# SAML21_Breakout_v2.net
KiCad netlist of a schematic drawn in EAGLE
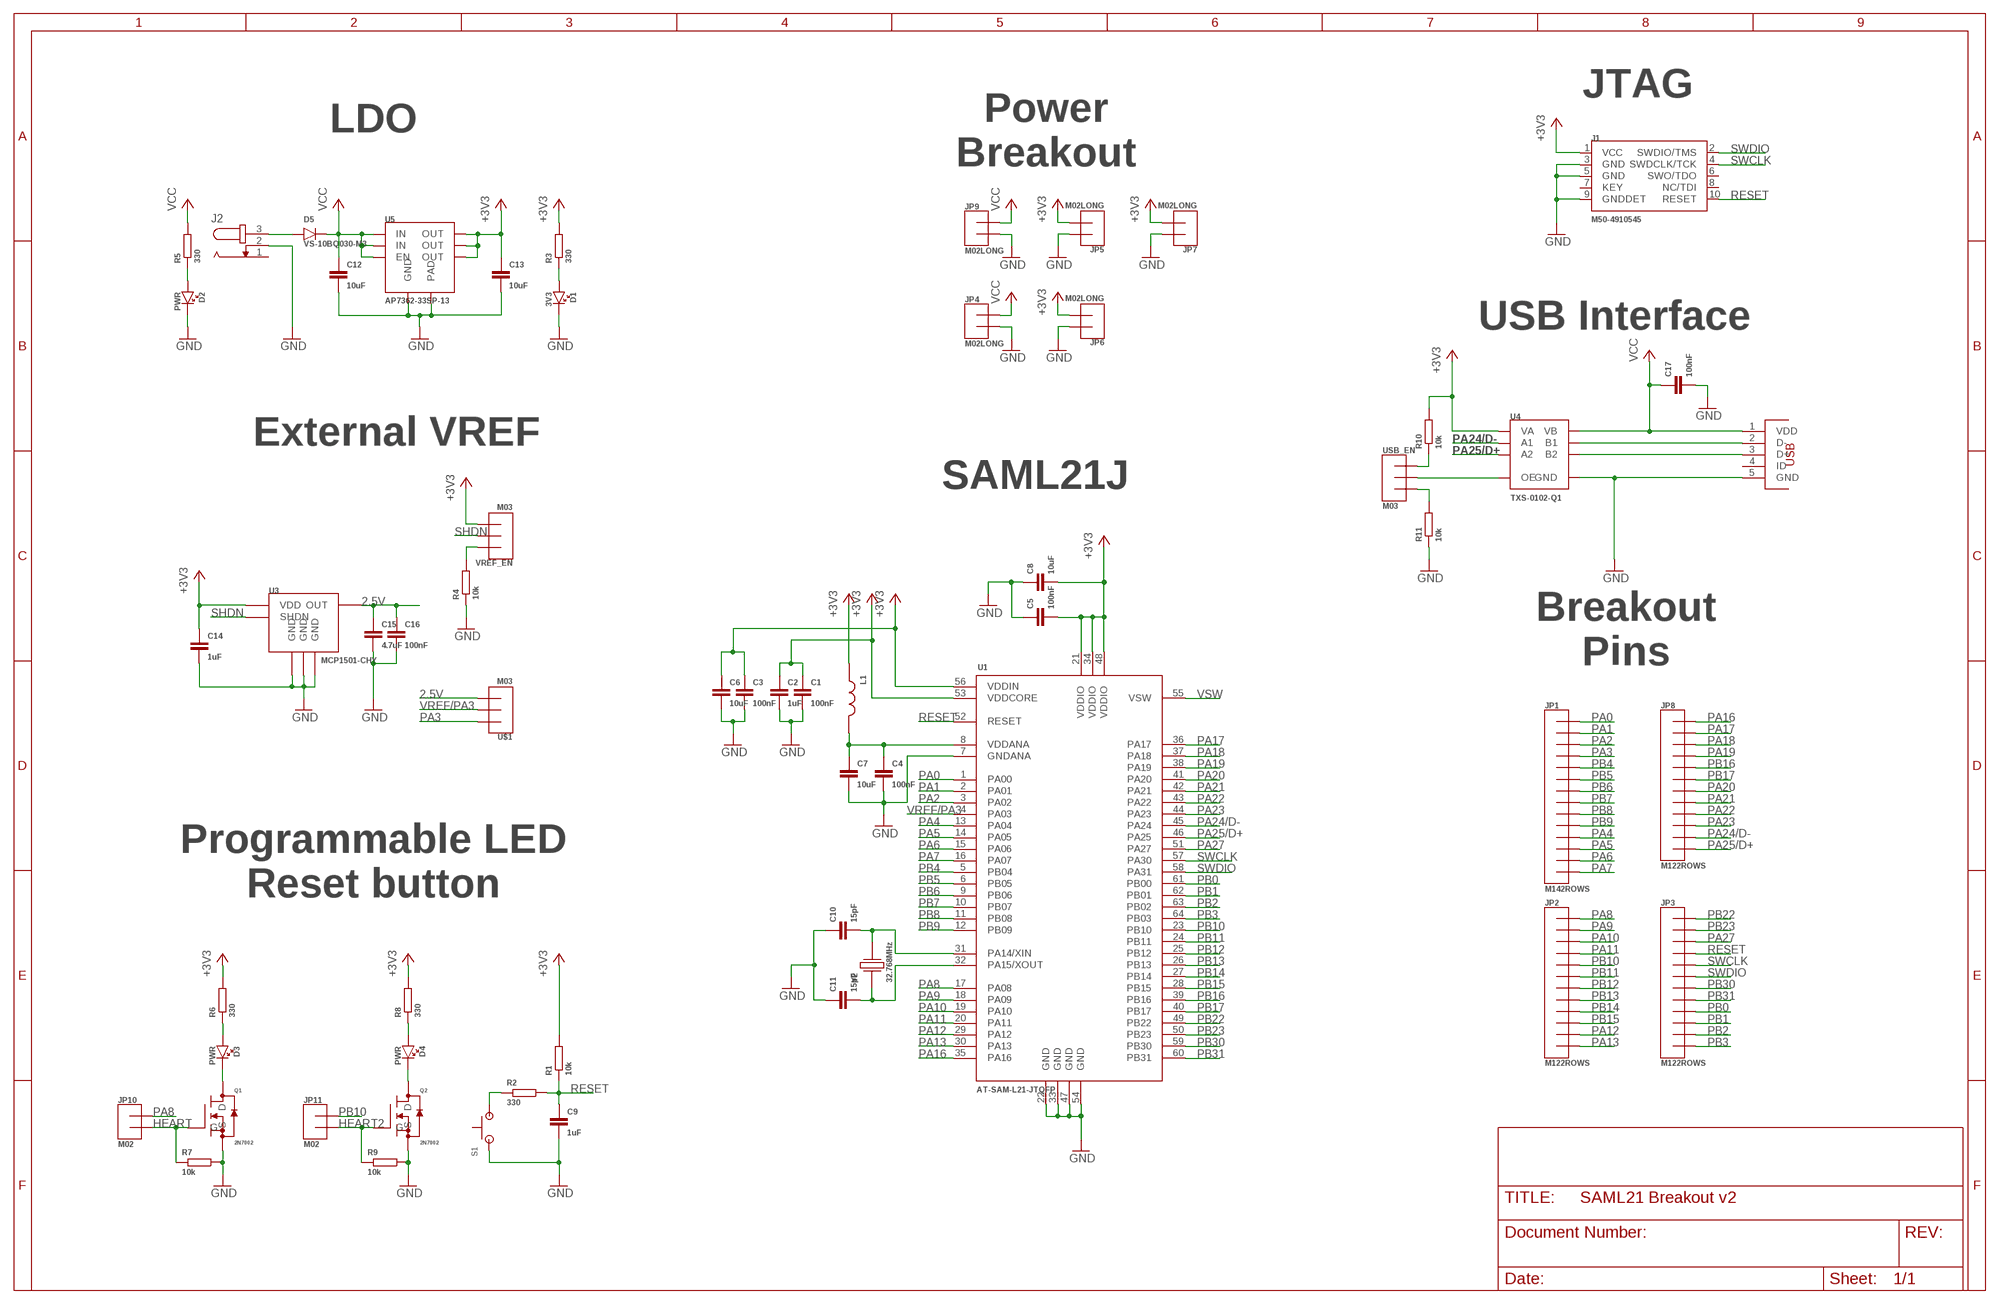
[diagram p0: schematic, sheet 1]

(export (version "E")
  (design (tool "Eeschema 10.0.6"))
  (components
    (comp (ref "C1")
      (value "100nF")
      (footprint "eagle-import:CAP-0603")
      (libsource (lib "eagle-import") (part "CAP0603"))
    )
    (comp (ref "C2")
      (value "1uF")
      (footprint "eagle-import:CAP-0603")
      (libsource (lib "eagle-import") (part "CAP0603"))
    )
    (comp (ref "C3")
      (value "100nF")
      (footprint "eagle-import:CAP-0603")
      (libsource (lib "eagle-import") (part "CAP0603"))
    )
    (comp (ref "C4")
      (value "100nF")
      (footprint "eagle-import:CAP-0603")
      (libsource (lib "eagle-import") (part "CAP0603"))
    )
    (comp (ref "C5")
      (value "100nF")
      (footprint "eagle-import:CAP-0603")
      (libsource (lib "eagle-import") (part "CAP0603"))
    )
    (comp (ref "C6")
      (value "10uF")
      (footprint "eagle-import:CAP-0603")
      (libsource (lib "eagle-import") (part "CAP0603"))
    )
    (comp (ref "C7")
      (value "10uF")
      (footprint "eagle-import:CAP-0603")
      (libsource (lib "eagle-import") (part "CAP0603"))
    )
    (comp (ref "C8")
      (value "10uF")
      (footprint "eagle-import:CAP-0603")
      (libsource (lib "eagle-import") (part "CAP0603"))
    )
    (comp (ref "C9")
      (value "1uF")
      (footprint "eagle-import:CAP-0603")
      (libsource (lib "eagle-import") (part "CAP0603"))
    )
    (comp (ref "C10")
      (value "15pF")
      (footprint "eagle-import:CAP-0603")
      (libsource (lib "eagle-import") (part "CAP0603"))
    )
    (comp (ref "C11")
      (value "15pF")
      (footprint "eagle-import:CAP-0603")
      (libsource (lib "eagle-import") (part "CAP0603"))
    )
    (comp (ref "C12")
      (value "10uF")
      (footprint "eagle-import:CAP-0603")
      (libsource (lib "eagle-import") (part "CAP0603"))
    )
    (comp (ref "C13")
      (value "10uF")
      (footprint "eagle-import:CAP-0603")
      (libsource (lib "eagle-import") (part "CAP0603"))
    )
    (comp (ref "C14")
      (value "1uF")
      (footprint "eagle-import:CAP-0603")
      (libsource (lib "eagle-import") (part "CAP0603"))
    )
    (comp (ref "C15")
      (value "4.7uF")
      (footprint "eagle-import:CAP-0805")
      (libsource (lib "eagle-import") (part "CAP0805"))
    )
    (comp (ref "C16")
      (value "100nF")
      (footprint "eagle-import:CAP-0603")
      (libsource (lib "eagle-import") (part "CAP0603"))
    )
    (comp (ref "C17")
      (value "100nF")
      (footprint "eagle-import:CAP-0603")
      (libsource (lib "eagle-import") (part "CAP0603"))
    )
    (comp (ref "D1")
      (value "3V3")
      (footprint "eagle-import:LED-1206")
      (libsource (lib "eagle-import") (part "LED1206"))
    )
    (comp (ref "D2")
      (value "PWR")
      (footprint "eagle-import:LED-1206")
      (libsource (lib "eagle-import") (part "LED1206"))
    )
    (comp (ref "D3")
      (value "PWR")
      (footprint "eagle-import:LED-1206")
      (libsource (lib "eagle-import") (part "LED1206"))
    )
    (comp (ref "D4")
      (value "PWR")
      (footprint "eagle-import:LED-1206")
      (libsource (lib "eagle-import") (part "LED1206"))
    )
    (comp (ref "D5")
      (value "VS-10BQ030-M3")
      (footprint "eagle-import:DO-214AA")
      (libsource (lib "eagle-import") (part "VS-10BQ030-M3"))
    )
    (comp (ref "J1")
      (value "M50-4910545")
      (footprint "eagle-import:M50-4910545")
      (libsource (lib "eagle-import") (part "M50-4910545"))
    )
    (comp (ref "J2")
      (value "JACK-PLUG0")
      (footprint "eagle-import:SPC4077")
      (libsource (lib "eagle-import") (part "JACK-PLUG0"))
    )
    (comp (ref "JP1")
      (value "M142ROWS")
      (footprint "eagle-import:2X07")
      (libsource (lib "eagle-import") (part "M142ROWS"))
    )
    (comp (ref "JP2")
      (value "M122ROWS")
      (footprint "eagle-import:2X06")
      (libsource (lib "eagle-import") (part "M122ROWS"))
    )
    (comp (ref "JP3")
      (value "M122ROWS")
      (footprint "eagle-import:2X06")
      (libsource (lib "eagle-import") (part "M122ROWS"))
    )
    (comp (ref "JP4")
      (value "M02LONG")
      (footprint "eagle-import:1X02-LONG")
      (libsource (lib "eagle-import") (part "M02LONG"))
    )
    (comp (ref "JP5")
      (value "M02LONG")
      (footprint "eagle-import:1X02-LONG")
      (libsource (lib "eagle-import") (part "M02LONG"))
    )
    (comp (ref "JP6")
      (value "M02LONG")
      (footprint "eagle-import:1X02-LONG")
      (libsource (lib "eagle-import") (part "M02LONG"))
    )
    (comp (ref "JP7")
      (value "M02LONG")
      (footprint "eagle-import:1X02-LONG")
      (libsource (lib "eagle-import") (part "M02LONG"))
    )
    (comp (ref "JP8")
      (value "M122ROWS")
      (footprint "eagle-import:2X06")
      (libsource (lib "eagle-import") (part "M122ROWS"))
    )
    (comp (ref "JP9")
      (value "M02LONG")
      (footprint "eagle-import:1X02-LONG")
      (libsource (lib "eagle-import") (part "M02LONG"))
    )
    (comp (ref "JP10")
      (value "M02")
      (footprint "eagle-import:1X02")
      (libsource (lib "eagle-import") (part "M02"))
    )
    (comp (ref "JP11")
      (value "M02")
      (footprint "eagle-import:1X02")
      (libsource (lib "eagle-import") (part "M02"))
    )
    (comp (ref "L1")
      (value "INDUCTOR0603")
      (footprint "eagle-import:IND-0603")
      (libsource (lib "eagle-import") (part "INDUCTOR0603"))
    )
    (comp (ref "Q1")
      (value "2N7002")
      (footprint "eagle-import:SOT-23-3")
      (libsource (lib "eagle-import") (part "2N7002"))
    )
    (comp (ref "Q2")
      (value "2N7002")
      (footprint "eagle-import:SOT-23-3")
      (libsource (lib "eagle-import") (part "2N7002"))
    )
    (comp (ref "R1")
      (value "10k")
      (footprint "eagle-import:RES-0805")
      (libsource (lib "eagle-import") (part "RESISTOR0805"))
    )
    (comp (ref "R2")
      (value "330")
      (footprint "eagle-import:RES-0805")
      (libsource (lib "eagle-import") (part "RESISTOR0805"))
    )
    (comp (ref "R3")
      (value "330")
      (footprint "eagle-import:RES-0805")
      (libsource (lib "eagle-import") (part "RESISTOR0805"))
    )
    (comp (ref "R4")
      (value "10k")
      (footprint "eagle-import:RES-0805")
      (libsource (lib "eagle-import") (part "RESISTOR0805"))
    )
    (comp (ref "R5")
      (value "330")
      (footprint "eagle-import:RES-0805")
      (libsource (lib "eagle-import") (part "RESISTOR0805"))
    )
    (comp (ref "R6")
      (value "330")
      (footprint "eagle-import:RES-0805")
      (libsource (lib "eagle-import") (part "RESISTOR0805"))
    )
    (comp (ref "R7")
      (value "10k")
      (footprint "eagle-import:RES-0805")
      (libsource (lib "eagle-import") (part "RESISTOR0805"))
    )
    (comp (ref "R8")
      (value "330")
      (footprint "eagle-import:RES-0805")
      (libsource (lib "eagle-import") (part "RESISTOR0805"))
    )
    (comp (ref "R9")
      (value "10k")
      (footprint "eagle-import:RES-0805")
      (libsource (lib "eagle-import") (part "RESISTOR0805"))
    )
    (comp (ref "R10")
      (value "10k")
      (footprint "eagle-import:RES-0805")
      (libsource (lib "eagle-import") (part "RESISTOR0805"))
    )
    (comp (ref "R11")
      (value "10k")
      (footprint "eagle-import:RES-0805")
      (libsource (lib "eagle-import") (part "RESISTOR0805"))
    )
    (comp (ref "S1")
      (value "SKHMQME010")
      (footprint "eagle-import:SKHMQME010")
      (libsource (lib "eagle-import") (part "SKHMQME010"))
    )
    (comp (ref "U$1")
      (value "M03")
      (footprint "eagle-import:1X03")
      (libsource (lib "eagle-import") (part "M03"))
    )
    (comp (ref "U$6")
      (value "MOLEX_USBMICRO")
      (footprint "eagle-import:MOLEX_47346-001")
      (libsource (lib "eagle-import") (part "MOLEX_USBMICRO"))
    )
    (comp (ref "U1")
      (value "AT-SAM-L21-JTQFP")
      (footprint "eagle-import:TQFP-64")
      (libsource (lib "eagle-import") (part "AT-SAM-L21-JTQFP"))
    )
    (comp (ref "U3")
      (value "MCP1501-CHY")
      (footprint "eagle-import:SOT-23-6")
      (libsource (lib "eagle-import") (part "MCP1501-CHY"))
    )
    (comp (ref "U4")
      (value "TXS-0102-Q1")
      (footprint "eagle-import:VSSOP-8")
      (libsource (lib "eagle-import") (part "TXS-0102-Q1"))
    )
    (comp (ref "U5")
      (value "AP7362-33SP-13")
      (footprint "eagle-import:SO-8EP")
      (libsource (lib "eagle-import") (part "AP7362-33SP-13"))
    )
    (comp (ref "USB_EN")
      (value "M03")
      (footprint "eagle-import:1X03")
      (libsource (lib "eagle-import") (part "M03"))
    )
    (comp (ref "VREF_EN")
      (value "M03")
      (footprint "eagle-import:1X03")
      (libsource (lib "eagle-import") (part "M03"))
    )
    (comp (ref "Y2")
      (value "32.768MHz")
      (footprint "eagle-import:CFPX-217")
      (libsource (lib "eagle-import") (part "LFXTAL054236-R"))
    )
  )
  (nets
    (net (code "1") (name "+3V3") (class "Default")
      (node (ref "C1") (pin "1") (pinfunction "1_1") (pintype "passive"))
      (node (ref "C13") (pin "1") (pinfunction "1_1") (pintype "passive"))
      (node (ref "C14") (pin "1") (pinfunction "1_1") (pintype "passive"))
      (node (ref "C2") (pin "1") (pinfunction "1_1") (pintype "passive"))
      (node (ref "C3") (pin "1") (pinfunction "1_1") (pintype "passive"))
      (node (ref "C5") (pin "2") (pinfunction "2_2") (pintype "passive"))
      (node (ref "C6") (pin "1") (pinfunction "1_1") (pintype "passive"))
      (node (ref "C8") (pin "2") (pinfunction "2_2") (pintype "passive"))
      (node (ref "J1") (pin "1") (pinfunction "VCC_1") (pintype "bidirectional"))
      (node (ref "JP5") (pin "2") (pinfunction "2_2") (pintype "bidirectional"))
      (node (ref "JP6") (pin "2") (pinfunction "2_2") (pintype "bidirectional"))
      (node (ref "JP7") (pin "2") (pinfunction "2_2") (pintype "bidirectional"))
      (node (ref "L1") (pin "1") (pinfunction "1_1") (pintype "passive"))
      (node (ref "R1") (pin "2") (pinfunction "2_2") (pintype "passive"))
      (node (ref "R10") (pin "2") (pinfunction "2_2") (pintype "passive"))
      (node (ref "R3") (pin "2") (pinfunction "2_2") (pintype "passive"))
      (node (ref "R6") (pin "2") (pinfunction "2_2") (pintype "passive"))
      (node (ref "R8") (pin "2") (pinfunction "2_2") (pintype "passive"))
      (node (ref "U1") (pin "21") (pinfunction "VDDIO_21") (pintype "power_in"))
      (node (ref "U1") (pin "34") (pinfunction "VDDIO_34") (pintype "power_in"))
      (node (ref "U1") (pin "48") (pinfunction "VDDIO_48") (pintype "power_in"))
      (node (ref "U1") (pin "53") (pinfunction "VDDCORE_53") (pintype "output"))
      (node (ref "U1") (pin "56") (pinfunction "VDDIN_56") (pintype "power_in"))
      (node (ref "U3") (pin "6") (pinfunction "VDD_6") (pintype "bidirectional"))
      (node (ref "U4") (pin "3") (pinfunction "VA_3") (pintype "bidirectional"))
      (node (ref "U5") (pin "5") (pinfunction "OUT_5") (pintype "bidirectional"))
      (node (ref "U5") (pin "6") (pinfunction "OUT_6") (pintype "bidirectional"))
      (node (ref "U5") (pin "7") (pinfunction "OUT_7") (pintype "bidirectional"))
      (node (ref "VREF_EN") (pin "3") (pinfunction "3_3") (pintype "bidirectional"))
    )
    (net (code "2") (name "/2.5V") (class "Default")
      (node (ref "C15") (pin "1") (pinfunction "1_1") (pintype "passive"))
      (node (ref "C16") (pin "1") (pinfunction "1_1") (pintype "passive"))
      (node (ref "U$1") (pin "3") (pinfunction "3_3") (pintype "bidirectional"))
      (node (ref "U3") (pin "1") (pinfunction "OUT_1") (pintype "bidirectional"))
    )
    (net (code "3") (name "/HEART") (class "Default")
      (node (ref "JP10") (pin "2") (pinfunction "2_2") (pintype "bidirectional"))
      (node (ref "Q1") (pin "G") (pinfunction "G_G") (pintype "bidirectional"))
      (node (ref "R7") (pin "1") (pinfunction "1_1") (pintype "passive"))
    )
    (net (code "4") (name "/HEART2") (class "Default")
      (node (ref "JP11") (pin "2") (pinfunction "2_2") (pintype "bidirectional"))
      (node (ref "Q2") (pin "G") (pinfunction "G_G") (pintype "bidirectional"))
      (node (ref "R9") (pin "1") (pinfunction "1_1") (pintype "passive"))
    )
    (net (code "5") (name "/PA0") (class "Default")
      (node (ref "JP1") (pin "1") (pinfunction "1_1") (pintype "bidirectional"))
      (node (ref "U1") (pin "1") (pinfunction "PA00_1") (pintype "bidirectional"))
    )
    (net (code "6") (name "/PA1") (class "Default")
      (node (ref "JP1") (pin "2") (pinfunction "2_2") (pintype "bidirectional"))
      (node (ref "U1") (pin "2") (pinfunction "PA01_2") (pintype "bidirectional"))
    )
    (net (code "7") (name "/PA2") (class "Default")
      (node (ref "JP1") (pin "3") (pinfunction "3_3") (pintype "bidirectional"))
      (node (ref "U1") (pin "3") (pinfunction "PA02_3") (pintype "bidirectional"))
    )
    (net (code "8") (name "/PA3") (class "Default")
      (node (ref "JP1") (pin "4") (pinfunction "4_4") (pintype "bidirectional"))
      (node (ref "U$1") (pin "1") (pinfunction "1_1") (pintype "bidirectional"))
    )
    (net (code "9") (name "/PA4") (class "Default")
      (node (ref "JP1") (pin "11") (pinfunction "11_11") (pintype "bidirectional"))
      (node (ref "U1") (pin "13") (pinfunction "PA04_13") (pintype "bidirectional"))
    )
    (net (code "10") (name "/PA5") (class "Default")
      (node (ref "JP1") (pin "12") (pinfunction "12_12") (pintype "bidirectional"))
      (node (ref "U1") (pin "14") (pinfunction "PA05_14") (pintype "bidirectional"))
    )
    (net (code "11") (name "/PA6") (class "Default")
      (node (ref "JP1") (pin "13") (pinfunction "13_13") (pintype "bidirectional"))
      (node (ref "U1") (pin "15") (pinfunction "PA06_15") (pintype "bidirectional"))
    )
    (net (code "12") (name "/PA7") (class "Default")
      (node (ref "JP1") (pin "14") (pinfunction "14_14") (pintype "bidirectional"))
      (node (ref "U1") (pin "16") (pinfunction "PA07_16") (pintype "bidirectional"))
    )
    (net (code "13") (name "/PA8") (class "Default")
      (node (ref "JP10") (pin "1") (pinfunction "1_1") (pintype "bidirectional"))
      (node (ref "JP2") (pin "1") (pinfunction "1_1") (pintype "bidirectional"))
      (node (ref "U1") (pin "17") (pinfunction "PA08_17") (pintype "bidirectional"))
    )
    (net (code "14") (name "/PA9") (class "Default")
      (node (ref "JP2") (pin "2") (pinfunction "2_2") (pintype "bidirectional"))
      (node (ref "U1") (pin "18") (pinfunction "PA09_18") (pintype "bidirectional"))
    )
    (net (code "15") (name "/PA10") (class "Default")
      (node (ref "JP2") (pin "3") (pinfunction "3_3") (pintype "bidirectional"))
      (node (ref "U1") (pin "19") (pinfunction "PA10_19") (pintype "bidirectional"))
    )
    (net (code "16") (name "/PA11") (class "Default")
      (node (ref "JP2") (pin "4") (pinfunction "4_4") (pintype "bidirectional"))
      (node (ref "U1") (pin "20") (pinfunction "PA11_20") (pintype "bidirectional"))
    )
    (net (code "17") (name "/PA12") (class "Default")
      (node (ref "JP2") (pin "11") (pinfunction "11_11") (pintype "bidirectional"))
      (node (ref "U1") (pin "29") (pinfunction "PA12_29") (pintype "bidirectional"))
    )
    (net (code "18") (name "/PA13") (class "Default")
      (node (ref "JP2") (pin "12") (pinfunction "12_12") (pintype "bidirectional"))
      (node (ref "U1") (pin "30") (pinfunction "PA13_30") (pintype "bidirectional"))
    )
    (net (code "19") (name "/PA16") (class "Default")
      (node (ref "JP8") (pin "1") (pinfunction "1_1") (pintype "bidirectional"))
      (node (ref "U1") (pin "35") (pinfunction "PA16_35") (pintype "bidirectional"))
    )
    (net (code "20") (name "/PA17") (class "Default")
      (node (ref "JP8") (pin "2") (pinfunction "2_2") (pintype "bidirectional"))
      (node (ref "U1") (pin "36") (pinfunction "PA17_36") (pintype "bidirectional"))
    )
    (net (code "21") (name "/PA18") (class "Default")
      (node (ref "JP8") (pin "3") (pinfunction "3_3") (pintype "bidirectional"))
      (node (ref "U1") (pin "37") (pinfunction "PA18_37") (pintype "bidirectional"))
    )
    (net (code "22") (name "/PA19") (class "Default")
      (node (ref "JP8") (pin "4") (pinfunction "4_4") (pintype "bidirectional"))
      (node (ref "U1") (pin "38") (pinfunction "PA19_38") (pintype "bidirectional"))
    )
    (net (code "23") (name "/PA20") (class "Default")
      (node (ref "JP8") (pin "7") (pinfunction "7_7") (pintype "bidirectional"))
      (node (ref "U1") (pin "41") (pinfunction "PA20_41") (pintype "bidirectional"))
    )
    (net (code "24") (name "/PA21") (class "Default")
      (node (ref "JP8") (pin "8") (pinfunction "8_8") (pintype "bidirectional"))
      (node (ref "U1") (pin "42") (pinfunction "PA21_42") (pintype "bidirectional"))
    )
    (net (code "25") (name "/PA22") (class "Default")
      (node (ref "JP8") (pin "9") (pinfunction "9_9") (pintype "bidirectional"))
      (node (ref "U1") (pin "43") (pinfunction "PA22_43") (pintype "bidirectional"))
    )
    (net (code "26") (name "/PA23") (class "Default")
      (node (ref "JP8") (pin "10") (pinfunction "10_10") (pintype "bidirectional"))
      (node (ref "U1") (pin "44") (pinfunction "PA23_44") (pintype "bidirectional"))
    )
    (net (code "27") (name "/PA24{slash}D-") (class "Default")
      (node (ref "JP8") (pin "11") (pinfunction "11_11") (pintype "bidirectional"))
      (node (ref "U1") (pin "45") (pinfunction "PA24_45") (pintype "bidirectional"))
      (node (ref "U4") (pin "5") (pinfunction "A1_5") (pintype "bidirectional"))
    )
    (net (code "28") (name "/PA25{slash}D+") (class "Default")
      (node (ref "JP8") (pin "12") (pinfunction "12_12") (pintype "bidirectional"))
      (node (ref "U1") (pin "46") (pinfunction "PA25_46") (pintype "bidirectional"))
      (node (ref "U4") (pin "4") (pinfunction "A2_4") (pintype "bidirectional"))
    )
    (net (code "29") (name "/PA27") (class "Default")
      (node (ref "JP3") (pin "3") (pinfunction "3_3") (pintype "bidirectional"))
      (node (ref "U1") (pin "51") (pinfunction "PA27_51") (pintype "bidirectional"))
    )
    (net (code "30") (name "/PB0") (class "Default")
      (node (ref "JP3") (pin "9") (pinfunction "9_9") (pintype "bidirectional"))
      (node (ref "U1") (pin "61") (pinfunction "PB00_61") (pintype "bidirectional"))
    )
    (net (code "31") (name "/PB1") (class "Default")
      (node (ref "JP3") (pin "10") (pinfunction "10_10") (pintype "bidirectional"))
      (node (ref "U1") (pin "62") (pinfunction "PB01_62") (pintype "bidirectional"))
    )
    (net (code "32") (name "/PB2") (class "Default")
      (node (ref "JP3") (pin "11") (pinfunction "11_11") (pintype "bidirectional"))
      (node (ref "U1") (pin "63") (pinfunction "PB02_63") (pintype "bidirectional"))
    )
    (net (code "33") (name "/PB3") (class "Default")
      (node (ref "JP3") (pin "12") (pinfunction "12_12") (pintype "bidirectional"))
      (node (ref "U1") (pin "64") (pinfunction "PB03_64") (pintype "bidirectional"))
    )
    (net (code "34") (name "/PB4") (class "Default")
      (node (ref "JP1") (pin "5") (pinfunction "5_5") (pintype "bidirectional"))
      (node (ref "U1") (pin "5") (pinfunction "PB04_5") (pintype "bidirectional"))
    )
    (net (code "35") (name "/PB5") (class "Default")
      (node (ref "JP1") (pin "6") (pinfunction "6_6") (pintype "bidirectional"))
      (node (ref "U1") (pin "6") (pinfunction "PB05_6") (pintype "bidirectional"))
    )
    (net (code "36") (name "/PB6") (class "Default")
      (node (ref "JP1") (pin "7") (pinfunction "7_7") (pintype "bidirectional"))
      (node (ref "U1") (pin "9") (pinfunction "PB06_9") (pintype "bidirectional"))
    )
    (net (code "37") (name "/PB7") (class "Default")
      (node (ref "JP1") (pin "8") (pinfunction "8_8") (pintype "bidirectional"))
      (node (ref "U1") (pin "10") (pinfunction "PB07_10") (pintype "bidirectional"))
    )
    (net (code "38") (name "/PB8") (class "Default")
      (node (ref "JP1") (pin "9") (pinfunction "9_9") (pintype "bidirectional"))
      (node (ref "U1") (pin "11") (pinfunction "PB08_11") (pintype "bidirectional"))
    )
    (net (code "39") (name "/PB9") (class "Default")
      (node (ref "JP1") (pin "10") (pinfunction "10_10") (pintype "bidirectional"))
      (node (ref "U1") (pin "12") (pinfunction "PB09_12") (pintype "bidirectional"))
    )
    (net (code "40") (name "/PB10") (class "Default")
      (node (ref "JP11") (pin "1") (pinfunction "1_1") (pintype "bidirectional"))
      (node (ref "JP2") (pin "5") (pinfunction "5_5") (pintype "bidirectional"))
      (node (ref "U1") (pin "23") (pinfunction "PB10_23") (pintype "bidirectional"))
    )
    (net (code "41") (name "/PB11") (class "Default")
      (node (ref "JP2") (pin "6") (pinfunction "6_6") (pintype "bidirectional"))
      (node (ref "U1") (pin "24") (pinfunction "PB11_24") (pintype "bidirectional"))
    )
    (net (code "42") (name "/PB12") (class "Default")
      (node (ref "JP2") (pin "7") (pinfunction "7_7") (pintype "bidirectional"))
      (node (ref "U1") (pin "25") (pinfunction "PB12_25") (pintype "bidirectional"))
    )
    (net (code "43") (name "/PB13") (class "Default")
      (node (ref "JP2") (pin "8") (pinfunction "8_8") (pintype "bidirectional"))
      (node (ref "U1") (pin "26") (pinfunction "PB13_26") (pintype "bidirectional"))
    )
    (net (code "44") (name "/PB14") (class "Default")
      (node (ref "JP2") (pin "9") (pinfunction "9_9") (pintype "bidirectional"))
      (node (ref "U1") (pin "27") (pinfunction "PB14_27") (pintype "bidirectional"))
    )
    (net (code "45") (name "/PB15") (class "Default")
      (node (ref "JP2") (pin "10") (pinfunction "10_10") (pintype "bidirectional"))
      (node (ref "U1") (pin "28") (pinfunction "PB15_28") (pintype "bidirectional"))
    )
    (net (code "46") (name "/PB16") (class "Default")
      (node (ref "JP8") (pin "5") (pinfunction "5_5") (pintype "bidirectional"))
      (node (ref "U1") (pin "39") (pinfunction "PB16_39") (pintype "bidirectional"))
    )
    (net (code "47") (name "/PB17") (class "Default")
      (node (ref "JP8") (pin "6") (pinfunction "6_6") (pintype "bidirectional"))
      (node (ref "U1") (pin "40") (pinfunction "PB17_40") (pintype "bidirectional"))
    )
    (net (code "48") (name "/PB22") (class "Default")
      (node (ref "JP3") (pin "1") (pinfunction "1_1") (pintype "bidirectional"))
      (node (ref "U1") (pin "49") (pinfunction "PB22_49") (pintype "bidirectional"))
    )
    (net (code "49") (name "/PB23") (class "Default")
      (node (ref "JP3") (pin "2") (pinfunction "2_2") (pintype "bidirectional"))
      (node (ref "U1") (pin "50") (pinfunction "PB23_50") (pintype "bidirectional"))
    )
    (net (code "50") (name "/PB30") (class "Default")
      (node (ref "JP3") (pin "7") (pinfunction "7_7") (pintype "bidirectional"))
      (node (ref "U1") (pin "59") (pinfunction "PB30_59") (pintype "bidirectional"))
    )
    (net (code "51") (name "/PB31") (class "Default")
      (node (ref "JP3") (pin "8") (pinfunction "8_8") (pintype "bidirectional"))
      (node (ref "U1") (pin "60") (pinfunction "PB31_60") (pintype "bidirectional"))
    )
    (net (code "52") (name "/RESET") (class "Default")
      (node (ref "C9") (pin "1") (pinfunction "1_1") (pintype "passive"))
      (node (ref "J1") (pin "10") (pinfunction "RESET_10") (pintype "bidirectional"))
      (node (ref "JP3") (pin "4") (pinfunction "4_4") (pintype "bidirectional"))
      (node (ref "R1") (pin "1") (pinfunction "1_1") (pintype "passive"))
      (node (ref "R2") (pin "2") (pinfunction "2_2") (pintype "passive"))
      (node (ref "U1") (pin "52") (pinfunction "RESET_52") (pintype "bidirectional"))
    )
    (net (code "53") (name "/SHDN") (class "Default")
      (node (ref "U3") (pin "4") (pinfunction "SHDN_4") (pintype "bidirectional"))
      (node (ref "VREF_EN") (pin "2") (pinfunction "2_2") (pintype "bidirectional"))
    )
    (net (code "54") (name "/SWCLK") (class "Default")
      (node (ref "J1") (pin "4") (pinfunction "SWDCLK/TCK_4") (pintype "bidirectional"))
      (node (ref "JP3") (pin "5") (pinfunction "5_5") (pintype "bidirectional"))
      (node (ref "U1") (pin "57") (pinfunction "PA30_57") (pintype "bidirectional"))
    )
    (net (code "55") (name "/SWDIO") (class "Default")
      (node (ref "J1") (pin "2") (pinfunction "SWDIO/TMS_2") (pintype "bidirectional"))
      (node (ref "JP3") (pin "6") (pinfunction "6_6") (pintype "bidirectional"))
      (node (ref "U1") (pin "58") (pinfunction "PA31_58") (pintype "bidirectional"))
    )
    (net (code "56") (name "/VREF{slash}PA3") (class "Default")
      (node (ref "U$1") (pin "2") (pinfunction "2_2") (pintype "bidirectional"))
      (node (ref "U1") (pin "4") (pinfunction "PA03_4") (pintype "bidirectional"))
    )
    (net (code "57") (name "/VSW") (class "Default")
      (node (ref "U1") (pin "55") (pinfunction "VSW_55") (pintype "bidirectional"))
    )
    (net (code "58") (name "GND") (class "Default")
      (node (ref "C1") (pin "2") (pinfunction "2_2") (pintype "passive"))
      (node (ref "C10") (pin "1") (pinfunction "1_1") (pintype "passive"))
      (node (ref "C11") (pin "1") (pinfunction "1_1") (pintype "passive"))
      (node (ref "C12") (pin "2") (pinfunction "2_2") (pintype "passive"))
      (node (ref "C13") (pin "2") (pinfunction "2_2") (pintype "passive"))
      (node (ref "C14") (pin "2") (pinfunction "2_2") (pintype "passive"))
      (node (ref "C15") (pin "2") (pinfunction "2_2") (pintype "passive"))
      (node (ref "C16") (pin "2") (pinfunction "2_2") (pintype "passive"))
      (node (ref "C17") (pin "2") (pinfunction "2_2") (pintype "passive"))
      (node (ref "C2") (pin "2") (pinfunction "2_2") (pintype "passive"))
      (node (ref "C3") (pin "2") (pinfunction "2_2") (pintype "passive"))
      (node (ref "C4") (pin "2") (pinfunction "2_2") (pintype "passive"))
      (node (ref "C5") (pin "1") (pinfunction "1_1") (pintype "passive"))
      (node (ref "C6") (pin "2") (pinfunction "2_2") (pintype "passive"))
      (node (ref "C7") (pin "2") (pinfunction "2_2") (pintype "passive"))
      (node (ref "C8") (pin "1") (pinfunction "1_1") (pintype "passive"))
      (node (ref "C9") (pin "2") (pinfunction "2_2") (pintype "passive"))
      (node (ref "D1") (pin "C") (pinfunction "C_C") (pintype "bidirectional"))
      (node (ref "D2") (pin "C") (pinfunction "C_C") (pintype "bidirectional"))
      (node (ref "J1") (pin "3") (pinfunction "GND_3") (pintype "bidirectional"))
      (node (ref "J1") (pin "5") (pinfunction "GND_5") (pintype "bidirectional"))
      (node (ref "J1") (pin "9") (pinfunction "GNDDET_9") (pintype "bidirectional"))
      (node (ref "J2") (pin "2") (pinfunction "2_2") (pintype "passive"))
      (node (ref "JP4") (pin "2") (pinfunction "2_2") (pintype "bidirectional"))
      (node (ref "JP5") (pin "1") (pinfunction "1_1") (pintype "bidirectional"))
      (node (ref "JP6") (pin "1") (pinfunction "1_1") (pintype "bidirectional"))
      (node (ref "JP7") (pin "1") (pinfunction "1_1") (pintype "bidirectional"))
      (node (ref "JP9") (pin "2") (pinfunction "2_2") (pintype "bidirectional"))
      (node (ref "Q1") (pin "S") (pinfunction "S_S") (pintype "bidirectional"))
      (node (ref "Q2") (pin "S") (pinfunction "S_S") (pintype "bidirectional"))
      (node (ref "R11") (pin "1") (pinfunction "1_1") (pintype "passive"))
      (node (ref "R4") (pin "1") (pinfunction "1_1") (pintype "passive"))
      (node (ref "R7") (pin "2") (pinfunction "2_2") (pintype "passive"))
      (node (ref "R9") (pin "2") (pinfunction "2_2") (pintype "passive"))
      (node (ref "S1") (pin "1") (pinfunction "1_1") (pintype "bidirectional"))
      (node (ref "U$6") (pin "5") (pinfunction "GND_5") (pintype "bidirectional"))
      (node (ref "U1") (pin "22") (pinfunction "GND_22") (pintype "power_in"))
      (node (ref "U1") (pin "33") (pinfunction "GND_33") (pintype "power_in"))
      (node (ref "U1") (pin "47") (pinfunction "GND_47") (pintype "power_in"))
      (node (ref "U1") (pin "54") (pinfunction "GND_54") (pintype "power_in"))
      (node (ref "U1") (pin "7") (pinfunction "GNDANA_7") (pintype "power_in"))
      (node (ref "U3") (pin "2") (pinfunction "GND_2") (pintype "bidirectional"))
      (node (ref "U3") (pin "3") (pinfunction "GND_3") (pintype "bidirectional"))
      (node (ref "U3") (pin "5") (pinfunction "GND_5") (pintype "bidirectional"))
      (node (ref "U4") (pin "2") (pinfunction "GND_2") (pintype "bidirectional"))
      (node (ref "U5") (pin "1") (pinfunction "GND_1") (pintype "bidirectional"))
      (node (ref "U5") (pin "PAD") (pinfunction "PAD_PAD") (pintype "bidirectional"))
    )
    (net (code "59") (name "Net-(D1-PadA)") (class "Default")
      (node (ref "D1") (pin "A") (pinfunction "A_A") (pintype "bidirectional"))
      (node (ref "R3") (pin "1") (pinfunction "1_1") (pintype "passive"))
    )
    (net (code "60") (name "Net-(D2-PadA)") (class "Default")
      (node (ref "D2") (pin "A") (pinfunction "A_A") (pintype "bidirectional"))
      (node (ref "R5") (pin "1") (pinfunction "1_1") (pintype "passive"))
    )
    (net (code "61") (name "Net-(D3-PadA)") (class "Default")
      (node (ref "D3") (pin "A") (pinfunction "A_A") (pintype "bidirectional"))
      (node (ref "R6") (pin "1") (pinfunction "1_1") (pintype "passive"))
    )
    (net (code "62") (name "Net-(D3-PadC)") (class "Default")
      (node (ref "D3") (pin "C") (pinfunction "C_C") (pintype "bidirectional"))
      (node (ref "Q1") (pin "D") (pinfunction "D_D") (pintype "bidirectional"))
    )
    (net (code "63") (name "Net-(D4-PadA)") (class "Default")
      (node (ref "D4") (pin "A") (pinfunction "A_A") (pintype "bidirectional"))
      (node (ref "R8") (pin "1") (pinfunction "1_1") (pintype "passive"))
    )
    (net (code "64") (name "Net-(D4-PadC)") (class "Default")
      (node (ref "D4") (pin "C") (pinfunction "C_C") (pintype "bidirectional"))
      (node (ref "Q2") (pin "D") (pinfunction "D_D") (pintype "bidirectional"))
    )
    (net (code "65") (name "Net-(D5-PadA)") (class "Default")
      (node (ref "D5") (pin "A") (pinfunction "A_A") (pintype "bidirectional"))
      (node (ref "J2") (pin "3") (pinfunction "3_3") (pintype "passive"))
    )
    (net (code "66") (name "Net-(R4-Pad2)") (class "Default")
      (node (ref "R4") (pin "2") (pinfunction "2_2") (pintype "passive"))
      (node (ref "VREF_EN") (pin "1") (pinfunction "1_1") (pintype "bidirectional"))
    )
    (net (code "67") (name "Net-(R10-Pad1)") (class "Default")
      (node (ref "R10") (pin "1") (pinfunction "1_1") (pintype "passive"))
      (node (ref "USB_EN") (pin "1") (pinfunction "1_1") (pintype "bidirectional"))
    )
    (net (code "68") (name "Net-(R11-Pad2)") (class "Default")
      (node (ref "R11") (pin "2") (pinfunction "2_2") (pintype "passive"))
      (node (ref "USB_EN") (pin "3") (pinfunction "3_3") (pintype "bidirectional"))
    )
    (net (code "69") (name "Net-(S1-2)") (class "Default")
      (node (ref "R2") (pin "1") (pinfunction "1_1") (pintype "passive"))
      (node (ref "S1") (pin "3") (pinfunction "2_3") (pintype "bidirectional"))
    )
    (net (code "70") (name "Net-(U$6-D+)") (class "Default")
      (node (ref "U$6") (pin "3") (pinfunction "D+_3") (pintype "bidirectional"))
      (node (ref "U4") (pin "1") (pinfunction "B2_1") (pintype "bidirectional"))
    )
    (net (code "71") (name "Net-(U$6-D-)") (class "Default")
      (node (ref "U$6") (pin "2") (pinfunction "D-_2") (pintype "bidirectional"))
      (node (ref "U4") (pin "8") (pinfunction "B1_8") (pintype "bidirectional"))
    )
    (net (code "72") (name "Net-(U1-PA14{slash}XIN)") (class "Default")
      (node (ref "C10") (pin "2") (pinfunction "2_2") (pintype "passive"))
      (node (ref "U1") (pin "31") (pinfunction "PA14/XIN_31") (pintype "bidirectional"))
      (node (ref "Y2") (pin "2") (pinfunction "2_2") (pintype "bidirectional"))
    )
    (net (code "73") (name "Net-(U1-PA15{slash}XOUT)") (class "Default")
      (node (ref "C11") (pin "2") (pinfunction "2_2") (pintype "passive"))
      (node (ref "U1") (pin "32") (pinfunction "PA15/XOUT_32") (pintype "bidirectional"))
      (node (ref "Y2") (pin "1") (pinfunction "1_1") (pintype "bidirectional"))
    )
    (net (code "74") (name "Net-(U1-VDDANA)") (class "Default")
      (node (ref "C4") (pin "1") (pinfunction "1_1") (pintype "passive"))
      (node (ref "C7") (pin "1") (pinfunction "1_1") (pintype "passive"))
      (node (ref "L1") (pin "2") (pinfunction "2_2") (pintype "passive"))
      (node (ref "U1") (pin "8") (pinfunction "VDDANA_8") (pintype "power_in"))
    )
    (net (code "75") (name "Net-(U4-OE)") (class "Default")
      (node (ref "U4") (pin "6") (pinfunction "OE_6") (pintype "bidirectional"))
      (node (ref "USB_EN") (pin "2") (pinfunction "2_2") (pintype "bidirectional"))
    )
    (net (code "76") (name "VCC") (class "Default")
      (node (ref "C12") (pin "1") (pinfunction "1_1") (pintype "passive"))
      (node (ref "C17") (pin "1") (pinfunction "1_1") (pintype "passive"))
      (node (ref "D5") (pin "C") (pinfunction "C_C") (pintype "bidirectional"))
      (node (ref "JP4") (pin "1") (pinfunction "1_1") (pintype "bidirectional"))
      (node (ref "JP9") (pin "1") (pinfunction "1_1") (pintype "bidirectional"))
      (node (ref "R5") (pin "2") (pinfunction "2_2") (pintype "passive"))
      (node (ref "U$6") (pin "1") (pinfunction "VDD_1") (pintype "bidirectional"))
      (node (ref "U4") (pin "7") (pinfunction "VB_7") (pintype "bidirectional"))
      (node (ref "U5") (pin "2") (pinfunction "EN_2") (pintype "bidirectional"))
      (node (ref "U5") (pin "3") (pinfunction "IN_3") (pintype "bidirectional"))
      (node (ref "U5") (pin "4") (pinfunction "IN_4") (pintype "bidirectional"))
    )
    (net (code "77") (name "unconnected-(J1-KEY-Pad7)") (class "Default")
      (node (ref "J1") (pin "7") (pinfunction "KEY_7") (pintype "bidirectional"))
    )
    (net (code "78") (name "unconnected-(J1-NC{slash}TDI-Pad8)") (class "Default")
      (node (ref "J1") (pin "8") (pinfunction "NC/TDI_8") (pintype "bidirectional"))
    )
    (net (code "79") (name "unconnected-(J1-SWO{slash}TDO-Pad6)") (class "Default")
      (node (ref "J1") (pin "6") (pinfunction "SWO/TDO_6") (pintype "bidirectional"))
    )
    (net (code "80") (name "unconnected-(J2-Pad1)") (class "Default")
      (node (ref "J2") (pin "1") (pinfunction "1_1") (pintype "passive"))
    )
    (net (code "81") (name "unconnected-(S1-3-Pad5)") (class "Default")
      (node (ref "S1") (pin "5") (pinfunction "3_5") (pintype "bidirectional"))
    )
    (net (code "82") (name "unconnected-(U$6-ID-Pad4)") (class "Default")
      (node (ref "U$6") (pin "4") (pinfunction "ID_4") (pintype "bidirectional"))
    )
    (net (code "83") (name "unconnected-(U5-NC-Pad8)") (class "Default")
      (node (ref "U5") (pin "8") (pinfunction "NC_8") (pintype "no_connect"))
    )
  )
)
